# Cart.net
KiCad netlist of a schematic drawn in Altium Designer
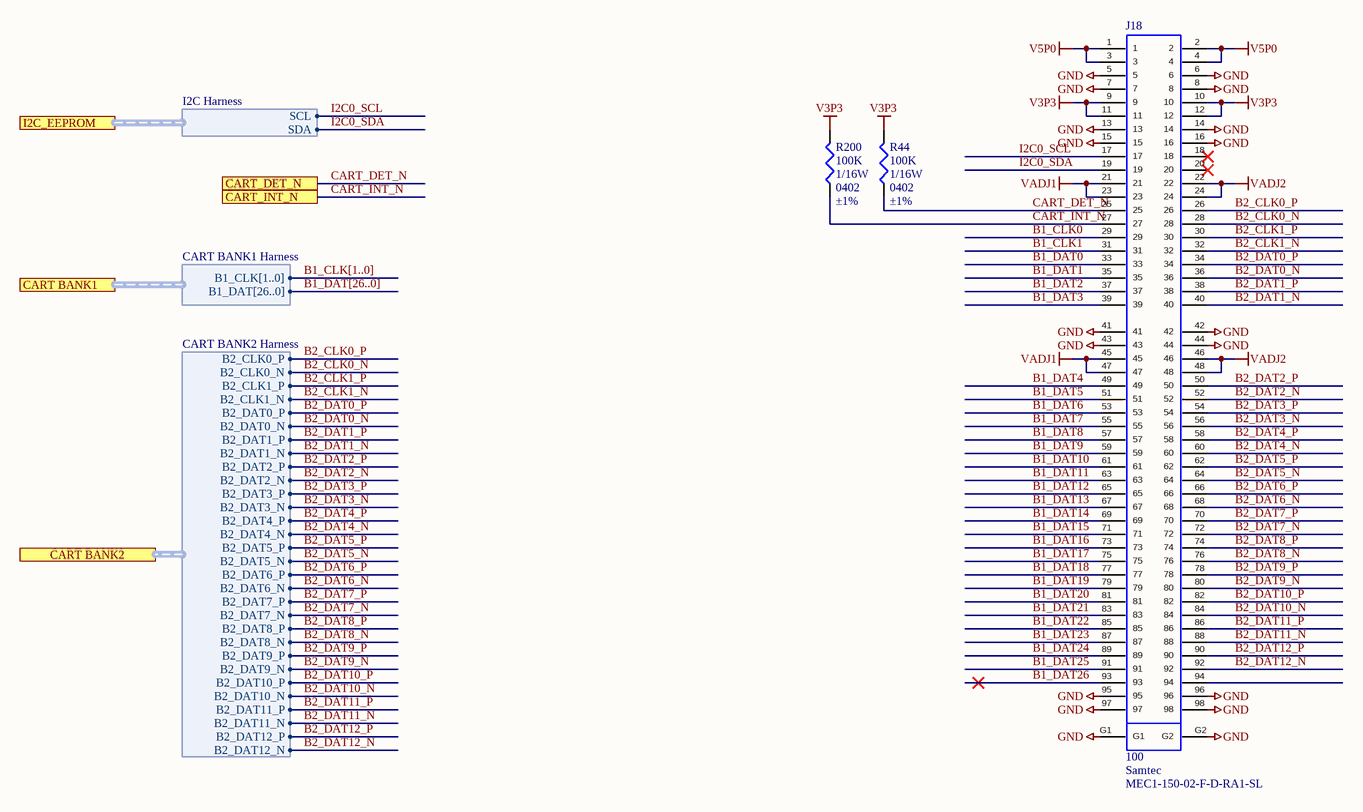
[diagram p0: Cart.SchDoc]

(export (version "E")
  (design (tool "Eeschema 10.0.6"))
  (components
    (comp (ref "J18")
      (value "J_MEC1-150-02-F-D-RA1-SL")
      (footprint "MEC1-150-XX-XX-D-RAX-SL")
      (description "1MM MINI-EDGE CARD ASSEMBLY")
      (fields
        (field (name "NUMBER OF CONTACTS") "100")
        (field (name "MANUFACTURER 1") "Samtec")
        (field (name "MANUFACTURER PART NUMBER 1") "MEC1-150-02-F-D-RA1-SL")
      )
      (libsource (lib "Cospan Design") (part "J_MEC1-150-02-F-D-RA1-SL"))
    )
    (comp (ref "R44")
      (value "R_0402_100K")
      (footprint "R_0402")
      (description "RES SMD 100K OHM 1% 1/16W 0402")
      (fields
        (field (name "MANUFACTURER") "Yageo")
        (field (name "MANUFACTURER PART NUMBER") "RC0402FR-07100KL")
        (field (name "RESISTANCE IN OHMS") "100K")
        (field (name "POWER (WATTS)") "1/16W")
        (field (name "CASE") "0402")
        (field (name "TOLERANCE") "±1%")
      )
      (libsource (lib "Cospan Design") (part "R_0402_100K"))
    )
    (comp (ref "R200")
      (value "R_0402_100K")
      (footprint "R_0402")
      (description "RES SMD 100K OHM 1% 1/16W 0402")
      (fields
        (field (name "MANUFACTURER") "Yageo")
        (field (name "MANUFACTURER PART NUMBER") "RC0402FR-07100KL")
        (field (name "RESISTANCE IN OHMS") "100K")
        (field (name "POWER (WATTS)") "1/16W")
        (field (name "CASE") "0402")
        (field (name "TOLERANCE") "±1%")
      )
      (libsource (lib "Cospan Design") (part "R_0402_100K"))
    )
  )
  (nets
    (net (code "6") (name "/B1_CLK0") (class "Default")
      (node (ref "J18") (pin "29") (pinfunction "29_29") (pintype "passive"))
    )
    (net (code "7") (name "/B1_CLK1") (class "Default")
      (node (ref "J18") (pin "31") (pinfunction "31_31") (pintype "passive"))
    )
    (net (code "9") (name "/B1_DAT0") (class "Default")
      (node (ref "J18") (pin "33") (pinfunction "33_33") (pintype "passive"))
    )
    (net (code "10") (name "/B1_DAT1") (class "Default")
      (node (ref "J18") (pin "35") (pinfunction "35_35") (pintype "passive"))
    )
    (net (code "11") (name "/B1_DAT2") (class "Default")
      (node (ref "J18") (pin "37") (pinfunction "37_37") (pintype "passive"))
    )
    (net (code "12") (name "/B1_DAT3") (class "Default")
      (node (ref "J18") (pin "39") (pinfunction "39_39") (pintype "passive"))
    )
    (net (code "13") (name "/B1_DAT4") (class "Default")
      (node (ref "J18") (pin "49") (pinfunction "49_49") (pintype "passive"))
    )
    (net (code "14") (name "/B1_DAT5") (class "Default")
      (node (ref "J18") (pin "51") (pinfunction "51_51") (pintype "passive"))
    )
    (net (code "15") (name "/B1_DAT6") (class "Default")
      (node (ref "J18") (pin "53") (pinfunction "53_53") (pintype "passive"))
    )
    (net (code "16") (name "/B1_DAT7") (class "Default")
      (node (ref "J18") (pin "55") (pinfunction "55_55") (pintype "passive"))
    )
    (net (code "17") (name "/B1_DAT8") (class "Default")
      (node (ref "J18") (pin "57") (pinfunction "57_57") (pintype "passive"))
    )
    (net (code "18") (name "/B1_DAT9") (class "Default")
      (node (ref "J18") (pin "59") (pinfunction "59_59") (pintype "passive"))
    )
    (net (code "19") (name "/B1_DAT10") (class "Default")
      (node (ref "J18") (pin "61") (pinfunction "61_61") (pintype "passive"))
    )
    (net (code "20") (name "/B1_DAT11") (class "Default")
      (node (ref "J18") (pin "63") (pinfunction "63_63") (pintype "passive"))
    )
    (net (code "21") (name "/B1_DAT12") (class "Default")
      (node (ref "J18") (pin "65") (pinfunction "65_65") (pintype "passive"))
    )
    (net (code "22") (name "/B1_DAT13") (class "Default")
      (node (ref "J18") (pin "67") (pinfunction "67_67") (pintype "passive"))
    )
    (net (code "23") (name "/B1_DAT14") (class "Default")
      (node (ref "J18") (pin "69") (pinfunction "69_69") (pintype "passive"))
    )
    (net (code "24") (name "/B1_DAT15") (class "Default")
      (node (ref "J18") (pin "71") (pinfunction "71_71") (pintype "passive"))
    )
    (net (code "25") (name "/B1_DAT16") (class "Default")
      (node (ref "J18") (pin "73") (pinfunction "73_73") (pintype "passive"))
    )
    (net (code "26") (name "/B1_DAT17") (class "Default")
      (node (ref "J18") (pin "75") (pinfunction "75_75") (pintype "passive"))
    )
    (net (code "27") (name "/B1_DAT18") (class "Default")
      (node (ref "J18") (pin "77") (pinfunction "77_77") (pintype "passive"))
    )
    (net (code "28") (name "/B1_DAT19") (class "Default")
      (node (ref "J18") (pin "79") (pinfunction "79_79") (pintype "passive"))
    )
    (net (code "29") (name "/B1_DAT20") (class "Default")
      (node (ref "J18") (pin "81") (pinfunction "81_81") (pintype "passive"))
    )
    (net (code "30") (name "/B1_DAT21") (class "Default")
      (node (ref "J18") (pin "83") (pinfunction "83_83") (pintype "passive"))
    )
    (net (code "31") (name "/B1_DAT22") (class "Default")
      (node (ref "J18") (pin "85") (pinfunction "85_85") (pintype "passive"))
    )
    (net (code "32") (name "/B1_DAT23") (class "Default")
      (node (ref "J18") (pin "87") (pinfunction "87_87") (pintype "passive"))
    )
    (net (code "33") (name "/B1_DAT24") (class "Default")
      (node (ref "J18") (pin "89") (pinfunction "89_89") (pintype "passive"))
    )
    (net (code "34") (name "/B1_DAT25") (class "Default")
      (node (ref "J18") (pin "91") (pinfunction "91_91") (pintype "passive"))
    )
    (net (code "35") (name "/B1_DAT26") (class "Default")
      (node (ref "J18") (pin "93") (pinfunction "93_93") (pintype "passive"))
    )
    (net (code "37") (name "/B2_CLK0_N") (class "Default")
      (node (ref "J18") (pin "28") (pinfunction "28_28") (pintype "passive"))
    )
    (net (code "38") (name "/B2_CLK0_P") (class "Default")
      (node (ref "J18") (pin "26") (pinfunction "26_26") (pintype "passive"))
    )
    (net (code "39") (name "/B2_CLK1_N") (class "Default")
      (node (ref "J18") (pin "32") (pinfunction "32_32") (pintype "passive"))
    )
    (net (code "40") (name "/B2_CLK1_P") (class "Default")
      (node (ref "J18") (pin "30") (pinfunction "30_30") (pintype "passive"))
    )
    (net (code "41") (name "/B2_DAT0_N") (class "Default")
      (node (ref "J18") (pin "36") (pinfunction "36_36") (pintype "passive"))
    )
    (net (code "42") (name "/B2_DAT0_P") (class "Default")
      (node (ref "J18") (pin "34") (pinfunction "34_34") (pintype "passive"))
    )
    (net (code "43") (name "/B2_DAT1_N") (class "Default")
      (node (ref "J18") (pin "40") (pinfunction "40_40") (pintype "passive"))
    )
    (net (code "44") (name "/B2_DAT1_P") (class "Default")
      (node (ref "J18") (pin "38") (pinfunction "38_38") (pintype "passive"))
    )
    (net (code "45") (name "/B2_DAT2_N") (class "Default")
      (node (ref "J18") (pin "52") (pinfunction "52_52") (pintype "passive"))
    )
    (net (code "46") (name "/B2_DAT2_P") (class "Default")
      (node (ref "J18") (pin "50") (pinfunction "50_50") (pintype "passive"))
    )
    (net (code "47") (name "/B2_DAT3_N") (class "Default")
      (node (ref "J18") (pin "56") (pinfunction "56_56") (pintype "passive"))
    )
    (net (code "48") (name "/B2_DAT3_P") (class "Default")
      (node (ref "J18") (pin "54") (pinfunction "54_54") (pintype "passive"))
    )
    (net (code "49") (name "/B2_DAT4_N") (class "Default")
      (node (ref "J18") (pin "60") (pinfunction "60_60") (pintype "passive"))
    )
    (net (code "50") (name "/B2_DAT4_P") (class "Default")
      (node (ref "J18") (pin "58") (pinfunction "58_58") (pintype "passive"))
    )
    (net (code "51") (name "/B2_DAT5_N") (class "Default")
      (node (ref "J18") (pin "64") (pinfunction "64_64") (pintype "passive"))
    )
    (net (code "52") (name "/B2_DAT5_P") (class "Default")
      (node (ref "J18") (pin "62") (pinfunction "62_62") (pintype "passive"))
    )
    (net (code "53") (name "/B2_DAT6_N") (class "Default")
      (node (ref "J18") (pin "68") (pinfunction "68_68") (pintype "passive"))
    )
    (net (code "54") (name "/B2_DAT6_P") (class "Default")
      (node (ref "J18") (pin "66") (pinfunction "66_66") (pintype "passive"))
    )
    (net (code "55") (name "/B2_DAT7_N") (class "Default")
      (node (ref "J18") (pin "72") (pinfunction "72_72") (pintype "passive"))
    )
    (net (code "56") (name "/B2_DAT7_P") (class "Default")
      (node (ref "J18") (pin "70") (pinfunction "70_70") (pintype "passive"))
    )
    (net (code "57") (name "/B2_DAT8_N") (class "Default")
      (node (ref "J18") (pin "76") (pinfunction "76_76") (pintype "passive"))
    )
    (net (code "58") (name "/B2_DAT8_P") (class "Default")
      (node (ref "J18") (pin "74") (pinfunction "74_74") (pintype "passive"))
    )
    (net (code "59") (name "/B2_DAT9_N") (class "Default")
      (node (ref "J18") (pin "80") (pinfunction "80_80") (pintype "passive"))
    )
    (net (code "60") (name "/B2_DAT9_P") (class "Default")
      (node (ref "J18") (pin "78") (pinfunction "78_78") (pintype "passive"))
    )
    (net (code "61") (name "/B2_DAT10_N") (class "Default")
      (node (ref "J18") (pin "84") (pinfunction "84_84") (pintype "passive"))
    )
    (net (code "62") (name "/B2_DAT10_P") (class "Default")
      (node (ref "J18") (pin "82") (pinfunction "82_82") (pintype "passive"))
    )
    (net (code "63") (name "/B2_DAT11_N") (class "Default")
      (node (ref "J18") (pin "88") (pinfunction "88_88") (pintype "passive"))
    )
    (net (code "64") (name "/B2_DAT11_P") (class "Default")
      (node (ref "J18") (pin "86") (pinfunction "86_86") (pintype "passive"))
    )
    (net (code "65") (name "/B2_DAT12_N") (class "Default")
      (node (ref "J18") (pin "92") (pinfunction "92_92") (pintype "passive"))
    )
    (net (code "66") (name "/B2_DAT12_P") (class "Default")
      (node (ref "J18") (pin "90") (pinfunction "90_90") (pintype "passive"))
    )
    (net (code "67") (name "/CART_DET_N") (class "Default")
      (node (ref "J18") (pin "25") (pinfunction "25_25") (pintype "passive"))
      (node (ref "R44") (pin "1") (pinfunction "1_1") (pintype "passive"))
    )
    (net (code "68") (name "/CART_INT_N") (class "Default")
      (node (ref "J18") (pin "27") (pinfunction "27_27") (pintype "passive"))
      (node (ref "R200") (pin "1") (pinfunction "1_1") (pintype "passive"))
    )
    (net (code "69") (name "/I2C0_SCL") (class "Default")
      (node (ref "J18") (pin "17") (pinfunction "17_17") (pintype "passive"))
    )
    (net (code "70") (name "/I2C0_SDA") (class "Default")
      (node (ref "J18") (pin "19") (pinfunction "19_19") (pintype "passive"))
    )
    (net (code "74") (name "GND") (class "Default")
      (node (ref "J18") (pin "13") (pinfunction "13_13") (pintype "passive"))
      (node (ref "J18") (pin "14") (pinfunction "14_14") (pintype "passive"))
      (node (ref "J18") (pin "15") (pinfunction "15_15") (pintype "passive"))
      (node (ref "J18") (pin "16") (pinfunction "16_16") (pintype "passive"))
      (node (ref "J18") (pin "41") (pinfunction "41_41") (pintype "passive"))
      (node (ref "J18") (pin "42") (pinfunction "42_42") (pintype "passive"))
      (node (ref "J18") (pin "43") (pinfunction "43_43") (pintype "passive"))
      (node (ref "J18") (pin "44") (pinfunction "44_44") (pintype "passive"))
      (node (ref "J18") (pin "5") (pinfunction "5_5") (pintype "passive"))
      (node (ref "J18") (pin "6") (pinfunction "6_6") (pintype "passive"))
      (node (ref "J18") (pin "7") (pinfunction "7_7") (pintype "passive"))
      (node (ref "J18") (pin "8") (pinfunction "8_8") (pintype "passive"))
      (node (ref "J18") (pin "95") (pinfunction "95_95") (pintype "passive"))
      (node (ref "J18") (pin "96") (pinfunction "96_96") (pintype "passive"))
      (node (ref "J18") (pin "97") (pinfunction "97_97") (pintype "passive"))
      (node (ref "J18") (pin "98") (pinfunction "98_98") (pintype "passive"))
      (node (ref "J18") (pin "G1") (pinfunction "G1_G1") (pintype "passive"))
      (node (ref "J18") (pin "G2") (pinfunction "G2_G2") (pintype "passive"))
    )
    (net (code "75") (name "V3P3") (class "Default")
      (node (ref "J18") (pin "10") (pinfunction "10_10") (pintype "passive"))
      (node (ref "J18") (pin "11") (pinfunction "11_11") (pintype "passive"))
      (node (ref "J18") (pin "12") (pinfunction "12_12") (pintype "passive"))
      (node (ref "J18") (pin "9") (pinfunction "9_9") (pintype "passive"))
      (node (ref "R200") (pin "2") (pinfunction "2_2") (pintype "passive"))
      (node (ref "R44") (pin "2") (pinfunction "2_2") (pintype "passive"))
    )
    (net (code "76") (name "V5P0") (class "Default")
      (node (ref "J18") (pin "1") (pinfunction "1_1") (pintype "passive"))
      (node (ref "J18") (pin "2") (pinfunction "2_2") (pintype "passive"))
      (node (ref "J18") (pin "3") (pinfunction "3_3") (pintype "passive"))
      (node (ref "J18") (pin "4") (pinfunction "4_4") (pintype "passive"))
    )
    (net (code "77") (name "VADJ1") (class "Default")
      (node (ref "J18") (pin "21") (pinfunction "21_21") (pintype "passive"))
      (node (ref "J18") (pin "23") (pinfunction "23_23") (pintype "passive"))
      (node (ref "J18") (pin "45") (pinfunction "45_45") (pintype "passive"))
      (node (ref "J18") (pin "47") (pinfunction "47_47") (pintype "passive"))
    )
    (net (code "78") (name "VADJ2") (class "Default")
      (node (ref "J18") (pin "22") (pinfunction "22_22") (pintype "passive"))
      (node (ref "J18") (pin "24") (pinfunction "24_24") (pintype "passive"))
      (node (ref "J18") (pin "46") (pinfunction "46_46") (pintype "passive"))
      (node (ref "J18") (pin "48") (pinfunction "48_48") (pintype "passive"))
    )
    (net (code "79") (name "unconnected-(J18-Pad18)") (class "Default")
      (node (ref "J18") (pin "18") (pinfunction "18_18") (pintype "passive+no_connect"))
    )
    (net (code "80") (name "unconnected-(J18-Pad20)") (class "Default")
      (node (ref "J18") (pin "20") (pinfunction "20_20") (pintype "passive+no_connect"))
    )
    (net (code "81") (name "unconnected-(J18-Pad94)") (class "Default")
      (node (ref "J18") (pin "94") (pinfunction "94_94") (pintype "passive"))
    )
  )
)
